# power.net
KiCad netlist of a schematic drawn in EAGLE
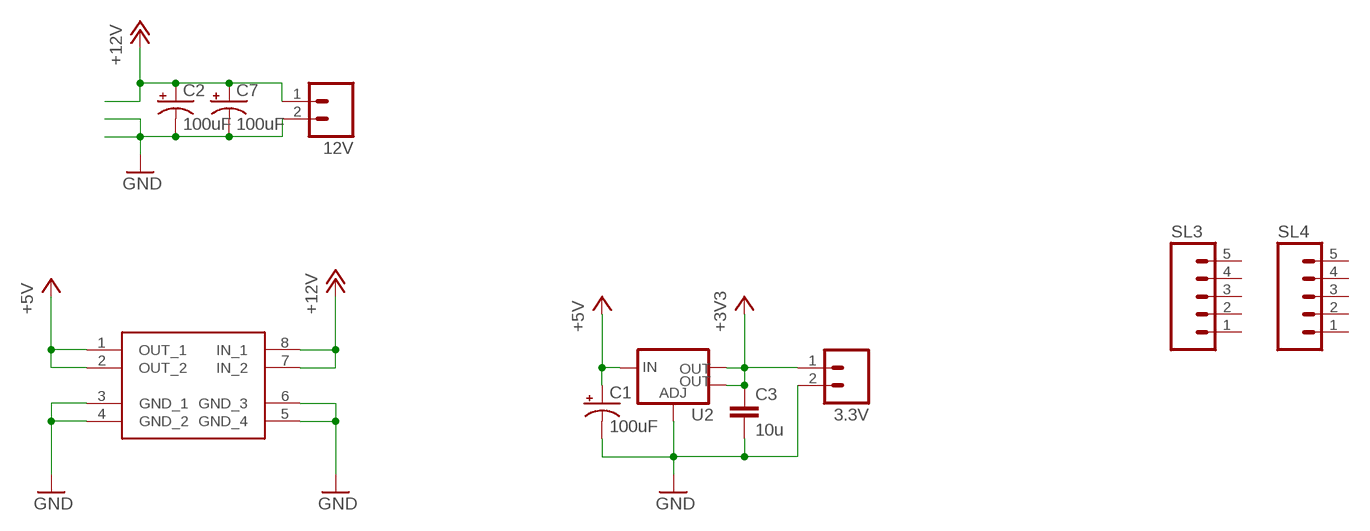
[diagram p0: schematic, sheet 1]

(export (version "E")
  (design (tool "Eeschema 10.0.6"))
  (components
    (comp (ref "3.3V")
      (value "M02")
      (footprint "eagle-import:02P")
      (libsource (lib "eagle-import") (part "M02"))
    )
    (comp (ref "12V")
      (value "M02")
      (footprint "eagle-import:02P")
      (libsource (lib "eagle-import") (part "M02"))
    )
    (comp (ref "C1")
      (value "100uF")
      (footprint "eagle-import:EIA7343")
      (libsource (lib "eagle-import") (part "100UF-POLAR-EIA7343-16V-10%(TANT)"))
    )
    (comp (ref "C2")
      (value "100uF")
      (footprint "eagle-import:EIA7343")
      (libsource (lib "eagle-import") (part "100UF-POLAR-EIA7343-16V-10%(TANT)"))
    )
    (comp (ref "C3")
      (value "10u")
      (footprint "eagle-import:C1206")
      (libsource (lib "eagle-import") (part "C-EUC1206"))
    )
    (comp (ref "C7")
      (value "100uF")
      (footprint "eagle-import:EIA7343")
      (libsource (lib "eagle-import") (part "100UF-POLAR-EIA7343-16V-10%(TANT)"))
    )
    (comp (ref "SL3")
      (value "M05")
      (footprint "eagle-import:05P")
      (libsource (lib "eagle-import") (part "M05"))
    )
    (comp (ref "SL4")
      (value "M05")
      (footprint "eagle-import:05P")
      (libsource (lib "eagle-import") (part "M05"))
    )
    (comp (ref "U$1")
      (value "MP1584_MODUL")
      (footprint "eagle-import:MP1584_MODUL")
      (libsource (lib "eagle-import") (part "MP1584_MODUL"))
    )
    (comp (ref "U2")
      (value "V_REG_LM1117SOT223")
      (footprint "eagle-import:SOT223")
      (libsource (lib "eagle-import") (part "V_REG_LM1117SOT223"))
    )
  )
  (nets
    (net (code "1") (name "+3V3") (class "Default")
      (node (ref "3.3V") (pin "1") (pinfunction "1_1") (pintype "passive"))
      (node (ref "C3") (pin "1") (pinfunction "1_1") (pintype "passive"))
      (node (ref "U2") (pin "2") (pinfunction "OUT_2") (pintype "output"))
      (node (ref "U2") (pin "4") (pinfunction "OUT_4") (pintype "output"))
    )
    (net (code "2") (name "+5V") (class "Default")
      (node (ref "C1") (pin "A") (pinfunction "+_A") (pintype "passive"))
      (node (ref "U$1") (pin "1") (pinfunction "OUT_1_1") (pintype "power_in"))
      (node (ref "U$1") (pin "2") (pinfunction "OUT_2_2") (pintype "power_in"))
      (node (ref "U2") (pin "3") (pinfunction "IN_3") (pintype "input"))
    )
    (net (code "3") (name "+12V") (class "Default")
      (node (ref "12V") (pin "1") (pinfunction "1_1") (pintype "passive"))
      (node (ref "C2") (pin "A") (pinfunction "+_A") (pintype "passive"))
      (node (ref "C7") (pin "A") (pinfunction "+_A") (pintype "passive"))
      (node (ref "U$1") (pin "7") (pinfunction "IN_2_7") (pintype "power_in"))
      (node (ref "U$1") (pin "8") (pinfunction "IN_1_8") (pintype "power_in"))
    )
    (net (code "4") (name "GND") (class "Default")
      (node (ref "12V") (pin "2") (pinfunction "2_2") (pintype "passive"))
      (node (ref "3.3V") (pin "2") (pinfunction "2_2") (pintype "passive"))
      (node (ref "C1") (pin "C") (pinfunction "-_C") (pintype "passive"))
      (node (ref "C2") (pin "C") (pinfunction "-_C") (pintype "passive"))
      (node (ref "C3") (pin "2") (pinfunction "2_2") (pintype "passive"))
      (node (ref "C7") (pin "C") (pinfunction "-_C") (pintype "passive"))
      (node (ref "U$1") (pin "3") (pinfunction "GND_1_3") (pintype "power_in"))
      (node (ref "U$1") (pin "4") (pinfunction "GND_2_4") (pintype "power_in"))
      (node (ref "U$1") (pin "5") (pinfunction "GND_4_5") (pintype "power_in"))
      (node (ref "U$1") (pin "6") (pinfunction "GND_3_6") (pintype "power_in"))
      (node (ref "U2") (pin "1") (pinfunction "ADJ_1") (pintype "input"))
    )
    (net (code "5") (name "unconnected-(SL3-Pad1)") (class "Default")
      (node (ref "SL3") (pin "1") (pinfunction "1_1") (pintype "passive"))
    )
    (net (code "6") (name "unconnected-(SL3-Pad2)") (class "Default")
      (node (ref "SL3") (pin "2") (pinfunction "2_2") (pintype "passive"))
    )
    (net (code "7") (name "unconnected-(SL3-Pad3)") (class "Default")
      (node (ref "SL3") (pin "3") (pinfunction "3_3") (pintype "passive"))
    )
    (net (code "8") (name "unconnected-(SL3-Pad4)") (class "Default")
      (node (ref "SL3") (pin "4") (pinfunction "4_4") (pintype "passive"))
    )
    (net (code "9") (name "unconnected-(SL3-Pad5)") (class "Default")
      (node (ref "SL3") (pin "5") (pinfunction "5_5") (pintype "passive"))
    )
    (net (code "10") (name "unconnected-(SL4-Pad1)") (class "Default")
      (node (ref "SL4") (pin "1") (pinfunction "1_1") (pintype "passive"))
    )
    (net (code "11") (name "unconnected-(SL4-Pad2)") (class "Default")
      (node (ref "SL4") (pin "2") (pinfunction "2_2") (pintype "passive"))
    )
    (net (code "12") (name "unconnected-(SL4-Pad3)") (class "Default")
      (node (ref "SL4") (pin "3") (pinfunction "3_3") (pintype "passive"))
    )
    (net (code "13") (name "unconnected-(SL4-Pad4)") (class "Default")
      (node (ref "SL4") (pin "4") (pinfunction "4_4") (pintype "passive"))
    )
    (net (code "14") (name "unconnected-(SL4-Pad5)") (class "Default")
      (node (ref "SL4") (pin "5") (pinfunction "5_5") (pintype "passive"))
    )
  )
)
